# taideng.net
KiCad netlist of a schematic drawn in Altium Designer
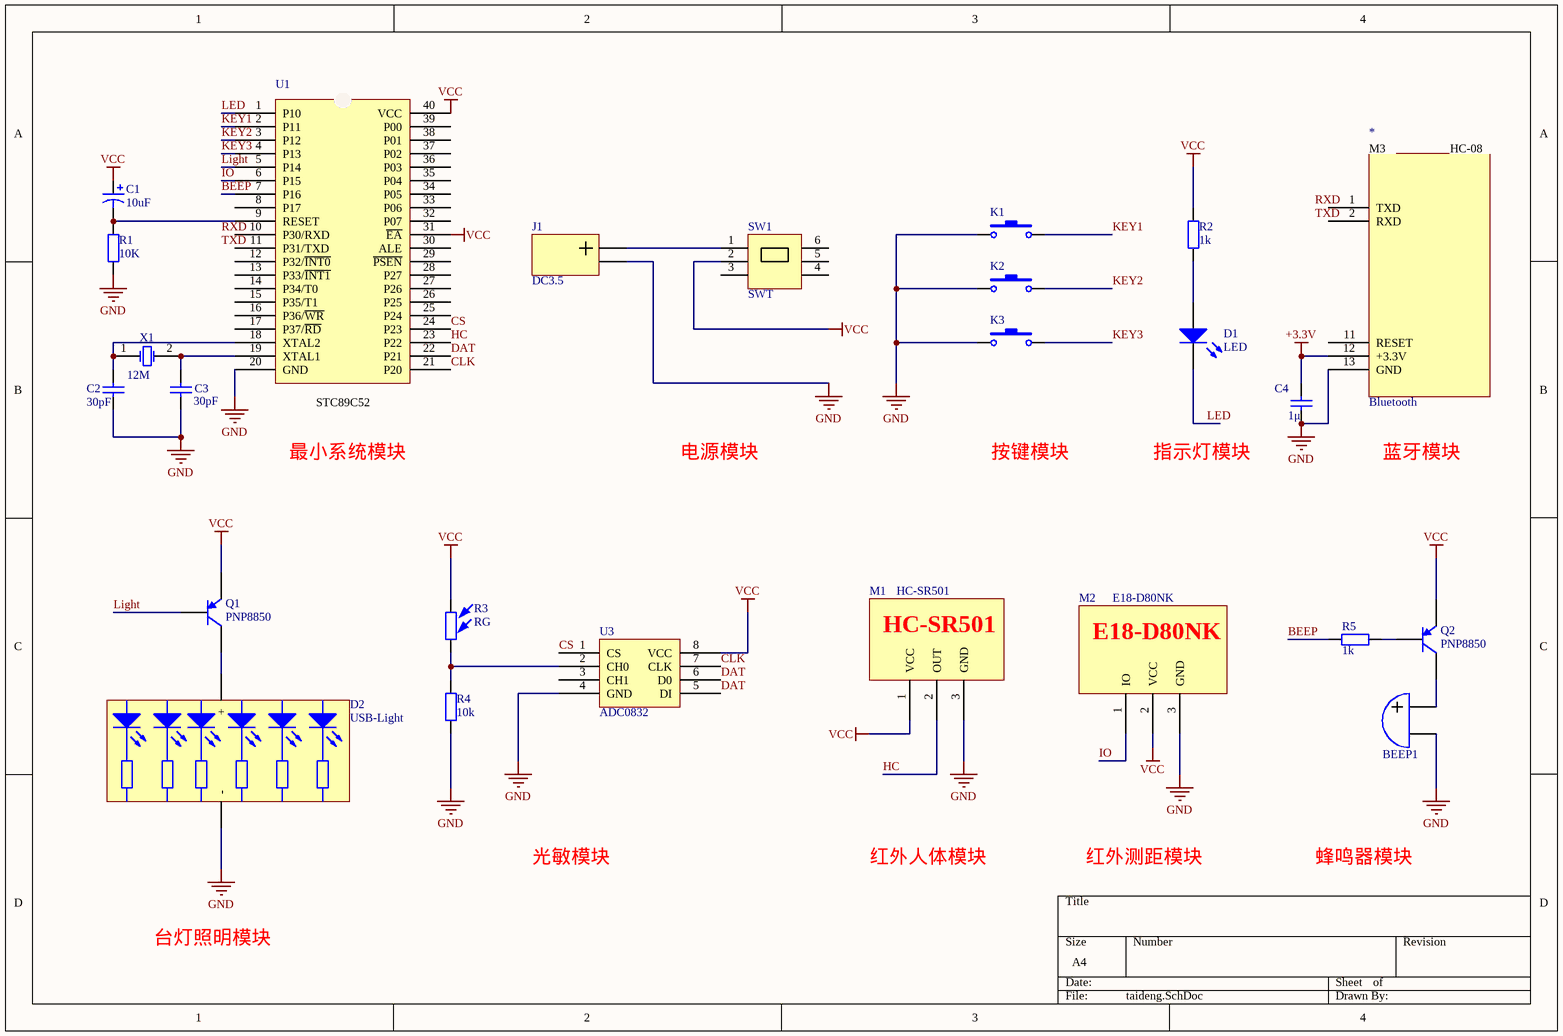
[diagram p0: taideng.SchDoc]

(export (version "E")
  (design (tool "Eeschema 10.0.6"))
  (components
    (comp (ref "*")
      (value "Bluetooth")
      (footprint "HC-XX:HC-08V20/22/41")
      (libsource (lib "Schlib1") (part "Bluetooth"))
    )
    (comp (ref "BEEP1") (value "BEEP") (footprint "BEEP") (libsource (lib "Schlib") (part "BEEP")))
    (comp (ref "C1") (value "10uF") (footprint "CAP_2") (libsource (lib "Schlib") (part "CAP_2")))
    (comp (ref "C2") (value "30pF") (footprint "CAP") (libsource (lib "Schlib") (part "CAP")))
    (comp (ref "C3") (value "30pF") (footprint "CAP") (libsource (lib "Schlib") (part "CAP")))
    (comp (ref "C4") (value "1μ") (footprint "CAP") (libsource (lib "SCH_Library") (part "CAP")))
    (comp (ref "D1") (value "LED") (footprint "LED") (libsource (lib "SCH_Library") (part "LED")))
    (comp (ref "D2")
      (value "USB-Light")
      (footprint "USB-A - 2")
      (libsource (lib "SCH_Library") (part "USB-Light"))
    )
    (comp (ref "J1") (value "DC3.5") (footprint "PCB库:DC3.5") (libsource (lib "原理图-1") (part "DC3.5")))
    (comp (ref "K1") (value "KEY") (footprint "KEY") (libsource (lib "SCH_Library") (part "KEY")))
    (comp (ref "K2") (value "KEY") (footprint "KEY") (libsource (lib "SCH_Library") (part "KEY")))
    (comp (ref "K3") (value "KEY") (footprint "KEY") (libsource (lib "SCH_Library") (part "KEY")))
    (comp (ref "M1")
      (value "HC-SR501")
      (footprint "HC-SR501")
      (libsource (lib "SCH_Library") (part "HC-SR501"))
    )
    (comp (ref "M2") (value "E18-D80NK") (footprint "SIP3") (libsource (lib "MANUAL") (part "E18-D80NK")))
    (comp (ref "Q1") (value "PNP8850") (footprint "NPN") (libsource (lib "SCH_Library") (part "PNP")))
    (comp (ref "Q2") (value "PNP8850") (footprint "NPN") (libsource (lib "SCH_Library") (part "PNP")))
    (comp (ref "R1") (value "10K") (footprint "RES") (libsource (lib "Schlib") (part "Res")))
    (comp (ref "R2") (value "1k") (footprint "RES") (libsource (lib "SCH_Library") (part "Res")))
    (comp (ref "R3") (value "RG") (footprint "RG") (libsource (lib "SCH_Library") (part "RG")))
    (comp (ref "R4") (value "10k") (footprint "RES") (libsource (lib "SCH_Library") (part "Res")))
    (comp (ref "R5") (value "1k") (footprint "RES") (libsource (lib "") (part "Res_1")))
    (comp (ref "SW1") (value "SWT") (footprint "SWT") (libsource (lib "SCH_Library") (part "SWT")))
    (comp (ref "U1") (value "STC89C52") (footprint "DIP40") (libsource (lib "Schlib") (part "STC89C52")))
    (comp (ref "U3") (value "ADC0832") (footprint "DIP8") (libsource (lib "SCH_Library") (part "ADC0832")))
    (comp (ref "X1") (value "12M") (footprint "XTAL") (libsource (lib "Schlib") (part "XTAL")))
  )
  (nets
    (net (code "1") (name "+3.3V") (class "Default")
      (node (ref "*") (pin "12") (pinfunction "+3.3V_12") (pintype "passive"))
      (node (ref "C4") (pin "2") (pinfunction "2_2") (pintype "passive"))
    )
    (net (code "2") (name "/BEEP") (class "Default")
      (node (ref "R5") (pin "1") (pinfunction "1_1") (pintype "passive"))
      (node (ref "U1") (pin "7") (pinfunction "P16_7") (pintype "passive"))
    )
    (net (code "3") (name "/CLK") (class "Default")
      (node (ref "U1") (pin "21") (pinfunction "P20_21") (pintype "passive"))
      (node (ref "U3") (pin "7") (pinfunction "CLK_7") (pintype "passive"))
    )
    (net (code "4") (name "/CS") (class "Default")
      (node (ref "U1") (pin "24") (pinfunction "P23_24") (pintype "passive"))
      (node (ref "U3") (pin "1") (pinfunction "CS_1") (pintype "passive"))
    )
    (net (code "5") (name "/DAT") (class "Default")
      (node (ref "U1") (pin "22") (pinfunction "P21_22") (pintype "passive"))
      (node (ref "U3") (pin "5") (pinfunction "DI_5") (pintype "passive"))
      (node (ref "U3") (pin "6") (pinfunction "D0_6") (pintype "passive"))
    )
    (net (code "6") (name "/HC") (class "Default")
      (node (ref "M1") (pin "2") (pinfunction "OUT_2") (pintype "passive"))
      (node (ref "U1") (pin "23") (pinfunction "P22_23") (pintype "passive"))
    )
    (net (code "7") (name "/IO") (class "Default")
      (node (ref "M2") (pin "1") (pinfunction "IO_1") (pintype "passive"))
      (node (ref "U1") (pin "6") (pinfunction "P15_6") (pintype "passive"))
    )
    (net (code "8") (name "/KEY1") (class "Default")
      (node (ref "K1") (pin "2") (pinfunction "2_2") (pintype "passive"))
      (node (ref "U1") (pin "2") (pinfunction "P11_2") (pintype "passive"))
    )
    (net (code "9") (name "/KEY2") (class "Default")
      (node (ref "K2") (pin "2") (pinfunction "2_2") (pintype "passive"))
      (node (ref "U1") (pin "3") (pinfunction "P12_3") (pintype "passive"))
    )
    (net (code "10") (name "/KEY3") (class "Default")
      (node (ref "K3") (pin "2") (pinfunction "2_2") (pintype "passive"))
      (node (ref "U1") (pin "4") (pinfunction "P13_4") (pintype "passive"))
    )
    (net (code "11") (name "/LED") (class "Default")
      (node (ref "D1") (pin "2") (pinfunction "2_2") (pintype "passive"))
      (node (ref "U1") (pin "1") (pinfunction "P10_1") (pintype "passive"))
    )
    (net (code "12") (name "/Light") (class "Default")
      (node (ref "Q1") (pin "B") (pinfunction "B_B") (pintype "passive"))
      (node (ref "U1") (pin "5") (pinfunction "P14_5") (pintype "passive"))
    )
    (net (code "15") (name "GND") (class "Default")
      (node (ref "*") (pin "13") (pinfunction "GND_13") (pintype "passive"))
      (node (ref "BEEP1") (pin "2") (pinfunction "2_2") (pintype "passive"))
      (node (ref "C2") (pin "1") (pinfunction "1_1") (pintype "passive"))
      (node (ref "C3") (pin "1") (pinfunction "1_1") (pintype "passive"))
      (node (ref "C4") (pin "1") (pinfunction "1_1") (pintype "passive"))
      (node (ref "D2") (pin "2") (pinfunction "-_2") (pintype "passive"))
      (node (ref "J1") (pin "2") (pinfunction "2_2") (pintype "passive"))
      (node (ref "K1") (pin "1") (pinfunction "1_1") (pintype "passive"))
      (node (ref "K2") (pin "1") (pinfunction "1_1") (pintype "passive"))
      (node (ref "K3") (pin "1") (pinfunction "1_1") (pintype "passive"))
      (node (ref "M1") (pin "3") (pinfunction "GND_3") (pintype "passive"))
      (node (ref "M2") (pin "3") (pinfunction "GND_3") (pintype "passive"))
      (node (ref "R1") (pin "1") (pinfunction "1_1") (pintype "passive"))
      (node (ref "R4") (pin "1") (pinfunction "1_1") (pintype "passive"))
      (node (ref "U1") (pin "20") (pinfunction "GND_20") (pintype "passive"))
      (node (ref "U3") (pin "4") (pinfunction "GND_4") (pintype "passive"))
    )
    (net (code "16") (name "Net-(BEEP1-Pad1)") (class "Default")
      (node (ref "BEEP1") (pin "1") (pinfunction "1_1") (pintype "passive"))
      (node (ref "Q2") (pin "C") (pinfunction "C_C") (pintype "passive"))
    )
    (net (code "17") (name "Net-(D1-Pad1)") (class "Default")
      (node (ref "D1") (pin "1") (pinfunction "1_1") (pintype "passive"))
      (node (ref "R2") (pin "1") (pinfunction "1_1") (pintype "passive"))
    )
    (net (code "18") (name "Net-(D2-+)") (class "Default")
      (node (ref "D2") (pin "1") (pinfunction "+_1") (pintype "passive"))
      (node (ref "Q1") (pin "C") (pinfunction "C_C") (pintype "passive"))
    )
    (net (code "19") (name "Net-(Q2-PadB)") (class "Default")
      (node (ref "Q2") (pin "B") (pinfunction "B_B") (pintype "passive"))
      (node (ref "R5") (pin "2") (pinfunction "2_2") (pintype "passive"))
    )
    (net (code "20") (name "Net-(SW1-0)") (class "Default")
      (node (ref "J1") (pin "1") (pinfunction "1_1") (pintype "passive"))
      (node (ref "SW1") (pin "1") (pinfunction "0_1") (pintype "passive"))
    )
    (net (code "21") (name "Net-(U1-RESET)") (class "Default")
      (node (ref "C1") (pin "2") (pinfunction "2_2") (pintype "passive"))
      (node (ref "R1") (pin "2") (pinfunction "2_2") (pintype "passive"))
      (node (ref "U1") (pin "9") (pinfunction "RESET_9") (pintype "passive"))
    )
    (net (code "22") (name "Net-(U1-XTAL1)") (class "Default")
      (node (ref "C3") (pin "2") (pinfunction "2_2") (pintype "passive"))
      (node (ref "U1") (pin "19") (pinfunction "XTAL1_19") (pintype "passive"))
      (node (ref "X1") (pin "2") (pinfunction "OSC2_2") (pintype "passive"))
    )
    (net (code "23") (name "Net-(U1-XTAL2)") (class "Default")
      (node (ref "C2") (pin "2") (pinfunction "2_2") (pintype "passive"))
      (node (ref "U1") (pin "18") (pinfunction "XTAL2_18") (pintype "passive"))
      (node (ref "X1") (pin "1") (pinfunction "OSC1_1") (pintype "passive"))
    )
    (net (code "24") (name "Net-(U3-CH0)") (class "Default")
      (node (ref "R3") (pin "2") (pinfunction "2_2") (pintype "passive"))
      (node (ref "R4") (pin "2") (pinfunction "2_2") (pintype "passive"))
      (node (ref "U3") (pin "2") (pinfunction "CH0_2") (pintype "passive"))
    )
    (net (code "25") (name "VCC") (class "Default")
      (node (ref "C1") (pin "1") (pinfunction "1_1") (pintype "passive"))
      (node (ref "M1") (pin "1") (pinfunction "VCC_1") (pintype "passive"))
      (node (ref "M2") (pin "2") (pinfunction "VCC_2") (pintype "passive"))
      (node (ref "Q1") (pin "E") (pinfunction "E_E") (pintype "passive"))
      (node (ref "Q2") (pin "E") (pinfunction "E_E") (pintype "passive"))
      (node (ref "R2") (pin "2") (pinfunction "2_2") (pintype "passive"))
      (node (ref "R3") (pin "1") (pinfunction "1_1") (pintype "passive"))
      (node (ref "SW1") (pin "2") (pinfunction "1_2") (pintype "passive"))
      (node (ref "U1") (pin "31") (pinfunction "~{EA}_31") (pintype "passive"))
      (node (ref "U1") (pin "40") (pinfunction "VCC_40") (pintype "passive"))
      (node (ref "U3") (pin "8") (pinfunction "VCC_8") (pintype "passive"))
    )
    (net (code "26") (name "unconnected-(*-RESET-Pad11)") (class "Default")
      (node (ref "*") (pin "11") (pinfunction "RESET_11") (pintype "passive"))
    )
    (net (code "27") (name "unconnected-(*-RXD-Pad2)") (class "Default")
      (node (ref "*") (pin "2") (pinfunction "RXD_2") (pintype "passive"))
    )
    (net (code "28") (name "unconnected-(*-TXD-Pad1)") (class "Default")
      (node (ref "*") (pin "1") (pinfunction "TXD_1") (pintype "passive"))
    )
    (net (code "29") (name "unconnected-(SW1-2-Pad3)") (class "Default")
      (node (ref "SW1") (pin "3") (pinfunction "2_3") (pintype "passive"))
    )
    (net (code "30") (name "unconnected-(SW1-3-Pad4)") (class "Default")
      (node (ref "SW1") (pin "4") (pinfunction "3_4") (pintype "passive"))
    )
    (net (code "31") (name "unconnected-(SW1-4-Pad5)") (class "Default")
      (node (ref "SW1") (pin "5") (pinfunction "4_5") (pintype "passive"))
    )
    (net (code "32") (name "unconnected-(SW1-5-Pad6)") (class "Default")
      (node (ref "SW1") (pin "6") (pinfunction "5_6") (pintype "passive"))
    )
    (net (code "33") (name "unconnected-(U1-ALE-Pad30)") (class "Default")
      (node (ref "U1") (pin "30") (pinfunction "ALE_30") (pintype "passive"))
    )
    (net (code "34") (name "unconnected-(U1-P00-Pad39)") (class "Default")
      (node (ref "U1") (pin "39") (pinfunction "P00_39") (pintype "passive"))
    )
    (net (code "35") (name "unconnected-(U1-P01-Pad38)") (class "Default")
      (node (ref "U1") (pin "38") (pinfunction "P01_38") (pintype "passive"))
    )
    (net (code "36") (name "unconnected-(U1-P02-Pad37)") (class "Default")
      (node (ref "U1") (pin "37") (pinfunction "P02_37") (pintype "passive"))
    )
    (net (code "37") (name "unconnected-(U1-P03-Pad36)") (class "Default")
      (node (ref "U1") (pin "36") (pinfunction "P03_36") (pintype "passive"))
    )
    (net (code "38") (name "unconnected-(U1-P04-Pad35)") (class "Default")
      (node (ref "U1") (pin "35") (pinfunction "P04_35") (pintype "passive"))
    )
    (net (code "39") (name "unconnected-(U1-P05-Pad34)") (class "Default")
      (node (ref "U1") (pin "34") (pinfunction "P05_34") (pintype "passive"))
    )
    (net (code "40") (name "unconnected-(U1-P06-Pad33)") (class "Default")
      (node (ref "U1") (pin "33") (pinfunction "P06_33") (pintype "passive"))
    )
    (net (code "41") (name "unconnected-(U1-P07-Pad32)") (class "Default")
      (node (ref "U1") (pin "32") (pinfunction "P07_32") (pintype "passive"))
    )
    (net (code "42") (name "unconnected-(U1-P17-Pad8)") (class "Default")
      (node (ref "U1") (pin "8") (pinfunction "P17_8") (pintype "passive"))
    )
    (net (code "43") (name "unconnected-(U1-P24-Pad25)") (class "Default")
      (node (ref "U1") (pin "25") (pinfunction "P24_25") (pintype "passive"))
    )
    (net (code "44") (name "unconnected-(U1-P25-Pad26)") (class "Default")
      (node (ref "U1") (pin "26") (pinfunction "P25_26") (pintype "passive"))
    )
    (net (code "45") (name "unconnected-(U1-P26-Pad27)") (class "Default")
      (node (ref "U1") (pin "27") (pinfunction "P26_27") (pintype "passive"))
    )
    (net (code "46") (name "unconnected-(U1-P27-Pad28)") (class "Default")
      (node (ref "U1") (pin "28") (pinfunction "P27_28") (pintype "passive"))
    )
    (net (code "47") (name "unconnected-(U1-P30{slash}RXD-Pad10)") (class "Default")
      (node (ref "U1") (pin "10") (pinfunction "P30/RXD_10") (pintype "passive"))
    )
    (net (code "48") (name "unconnected-(U1-P31{slash}TXD-Pad11)") (class "Default")
      (node (ref "U1") (pin "11") (pinfunction "P31/TXD_11") (pintype "passive"))
    )
    (net (code "49") (name "unconnected-(U1-P32{slash}~{INT0}-Pad12)") (class "Default")
      (node (ref "U1") (pin "12") (pinfunction "P32/~{INT0}_12") (pintype "passive"))
    )
    (net (code "50") (name "unconnected-(U1-P33{slash}~{INT1}-Pad13)") (class "Default")
      (node (ref "U1") (pin "13") (pinfunction "P33/~{INT1}_13") (pintype "passive"))
    )
    (net (code "51") (name "unconnected-(U1-P34{slash}T0-Pad14)") (class "Default")
      (node (ref "U1") (pin "14") (pinfunction "P34/T0_14") (pintype "passive"))
    )
    (net (code "52") (name "unconnected-(U1-P35{slash}T1-Pad15)") (class "Default")
      (node (ref "U1") (pin "15") (pinfunction "P35/T1_15") (pintype "passive"))
    )
    (net (code "53") (name "unconnected-(U1-P36{slash}~{WR}-Pad16)") (class "Default")
      (node (ref "U1") (pin "16") (pinfunction "P36/~{WR}_16") (pintype "passive"))
    )
    (net (code "54") (name "unconnected-(U1-P37{slash}~{RD}-Pad17)") (class "Default")
      (node (ref "U1") (pin "17") (pinfunction "P37/~{RD}_17") (pintype "passive"))
    )
    (net (code "55") (name "unconnected-(U1-~{PSEN}-Pad29)") (class "Default")
      (node (ref "U1") (pin "29") (pinfunction "~{PSEN}_29") (pintype "passive"))
    )
    (net (code "56") (name "unconnected-(U3-CH1-Pad3)") (class "Default")
      (node (ref "U3") (pin "3") (pinfunction "CH1_3") (pintype "passive"))
    )
  )
)
